# AutoCar.net
KiCad netlist of a schematic drawn in Altium Designer
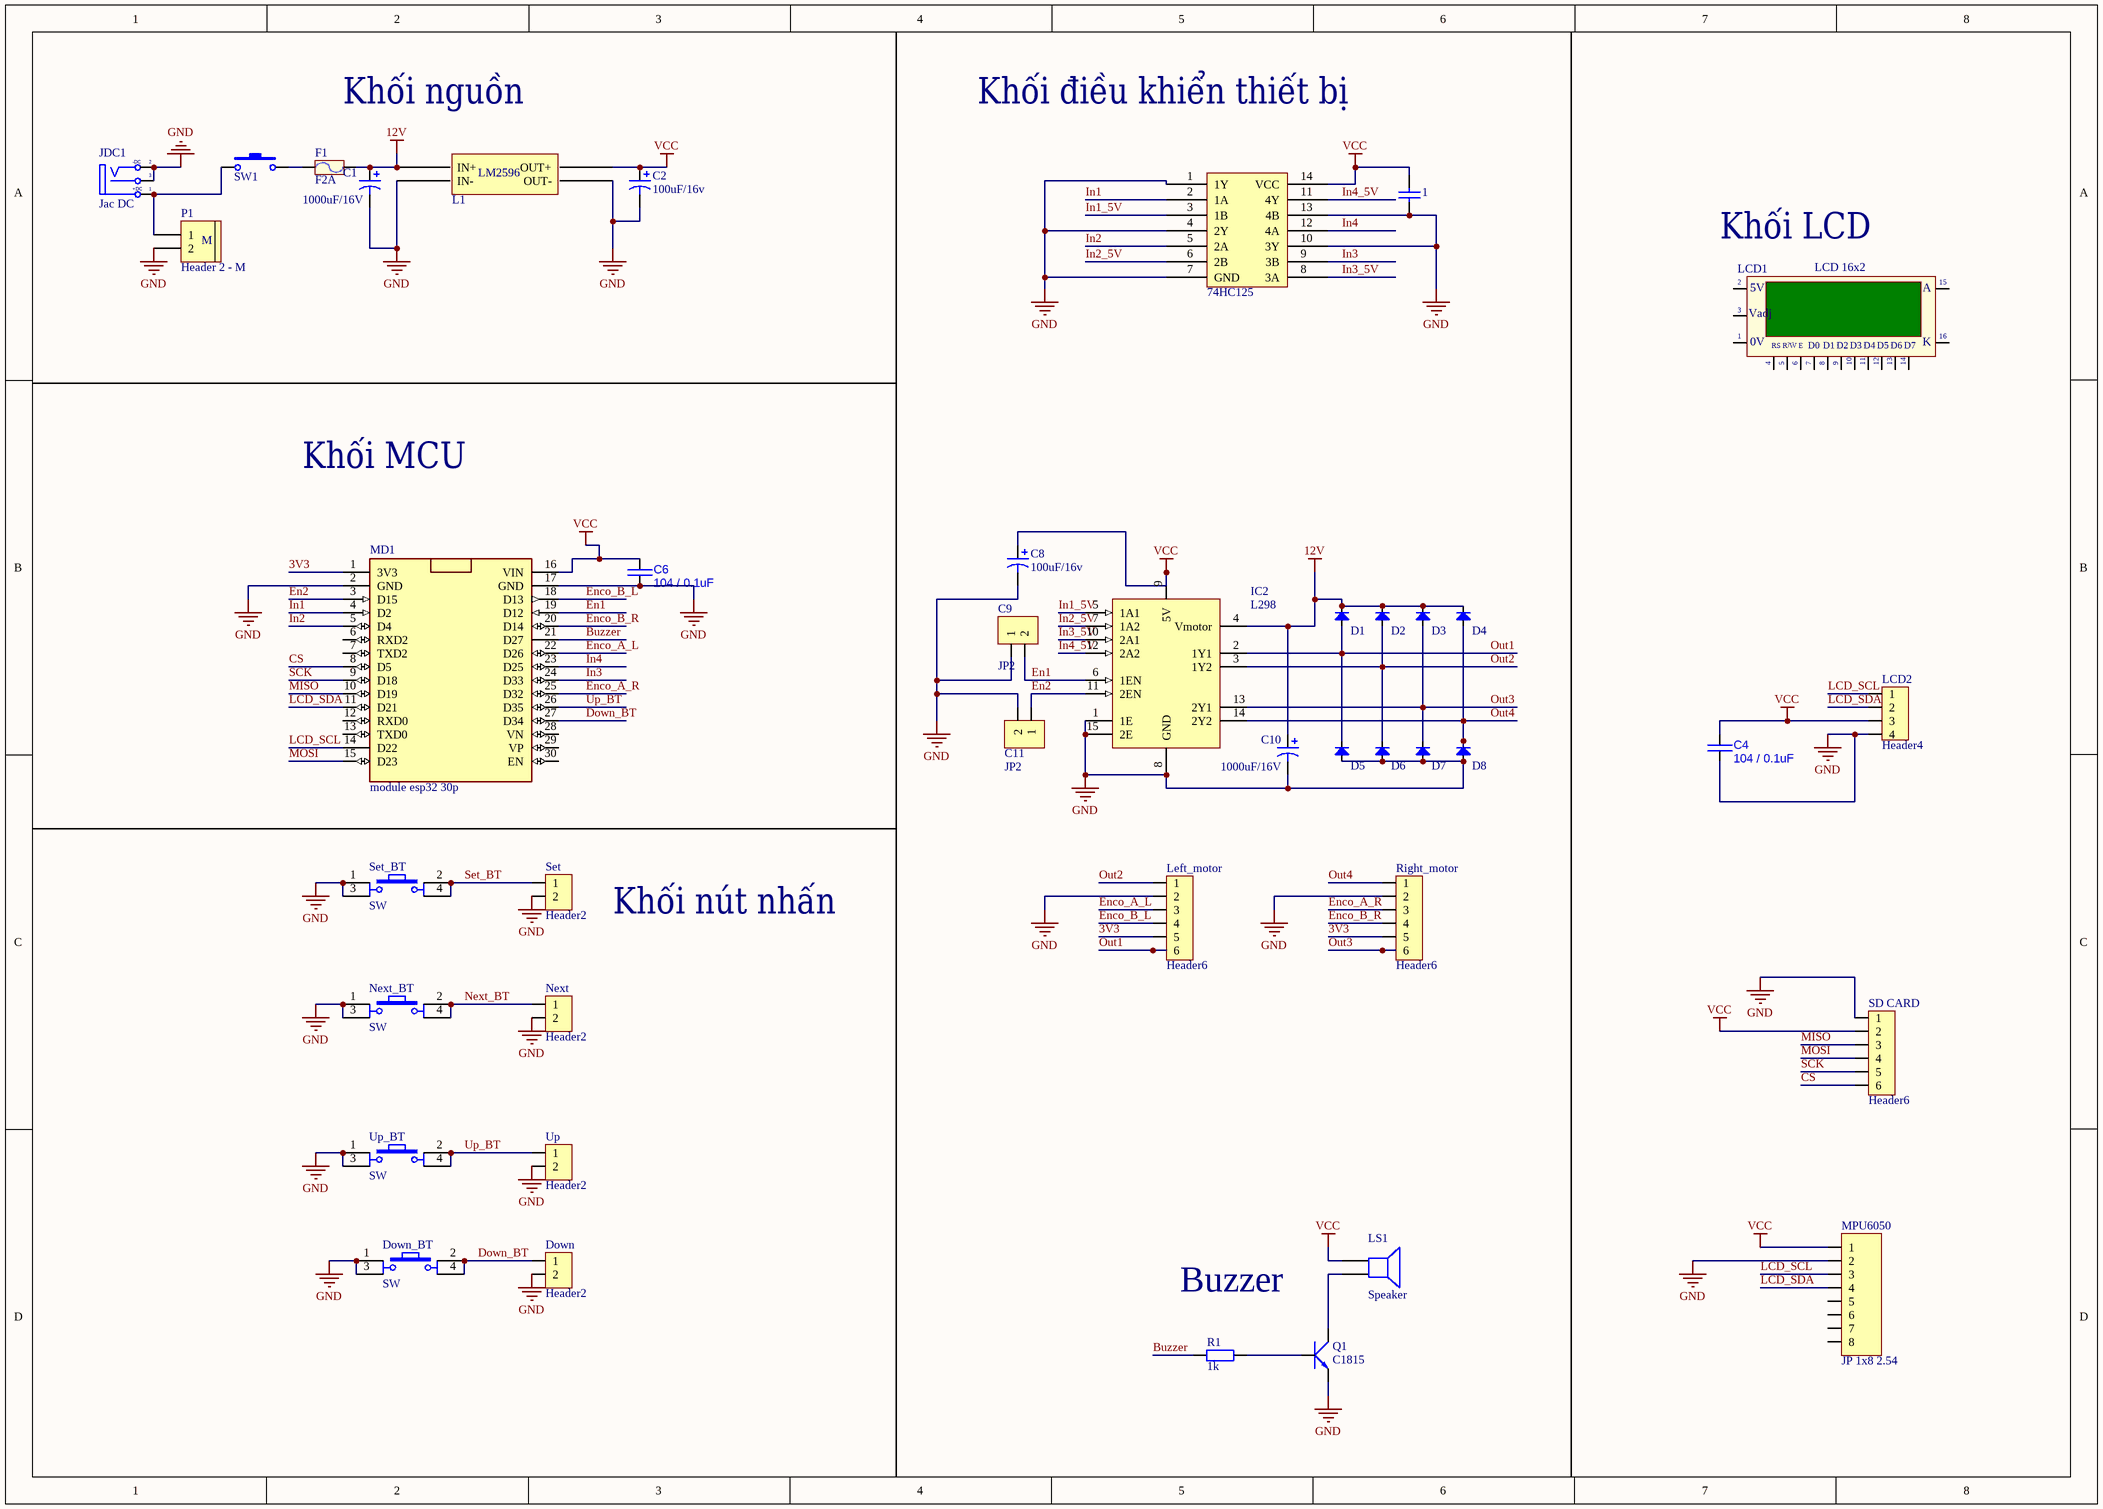
[diagram p0: AutoCar.SchDoc]

(export (version "E")
  (design (tool "Eeschema 10.0.6"))
  (components
    (comp (ref "1")
      (value "Capacitor Ceramic")
      (footprint "C1206")
      (description "Capacitor")
      (fields (field (name "PUBLISHER") "Altium Limited"))
      (libsource (lib "My Library") (part "CapSMD"))
    )
    (comp (ref "74HC125")
      (value "74HC02 DIP14")
      (footprint "dip14")
      (description "Cắm")
      (libsource (lib "IC") (part "74HC02 DIP"))
    )
    (comp (ref "C1")
      (value "1000uF/16V")
      (footprint "C8mm")
      (description "Polarized Capacitor (Axial)")
      (fields (field (name "PUBLISHER") "Altium Limited"))
      (libsource (lib "My Library") (part "Cap Pol 12mm"))
    )
    (comp (ref "C2")
      (value "100uF/16v")
      (footprint "C5mm")
      (description "Polarized Capacitor (Axial)")
      (fields (field (name "PUBLISHER") "Altium Limited"))
      (libsource (lib "My Library") (part "Cap Pol 5mm"))
    )
    (comp (ref "C4")
      (value "104 / 0.1uF")
      (footprint "SMD Capacistor 1206")
      (description "Capacitor SMD Cer 1.8nF 10% 50V X7R 0805")
      (fields (field (name "TOLERANCE") "±10%") (field (name "Comment") "approved sub OK"))
      (libsource (lib "My library altium") (part "CAP C_0805"))
    )
    (comp (ref "C6")
      (value "104 / 0.1uF")
      (footprint "SMD Capacistor 1206")
      (description "Capacitor SMD Cer 1.8nF 10% 50V X7R 0805")
      (fields (field (name "TOLERANCE") "±10%") (field (name "Comment") "approved sub OK"))
      (libsource (lib "My library altium") (part "CAP C_0805"))
    )
    (comp (ref "C8")
      (value "100uF/16v")
      (footprint "C5mm")
      (description "Polarized Capacitor (Axial)")
      (fields (field (name "PUBLISHER") "Altium Limited"))
      (libsource (lib "My Library") (part "Cap Pol 5mm"))
    )
    (comp (ref "C9")
      (value "JP2")
      (footprint "JP2-CLOSED")
      (description "WR-PHD 2.54 mm Angled Socket Header")
      (fields
        (field (name "MANUFACTURER") "Würth Elektronik eiSos GmbH")
        (field (name "PARTNO") "613002143121")
        (field (name "CREATED BY") "Karrer Zheng")
      )
      (libsource (lib "") (part "JP2_1"))
    )
    (comp (ref "C10")
      (value "1000uF/16V")
      (footprint "C8mm")
      (description "Polarized Capacitor (Axial)")
      (fields (field (name "PUBLISHER") "Altium Limited"))
      (libsource (lib "My Library") (part "Cap Pol 12mm"))
    )
    (comp (ref "C11")
      (value "JP2")
      (footprint "JP2-CLOSED")
      (description "WR-PHD 2.54 mm Angled Socket Header")
      (fields
        (field (name "MANUFACTURER") "Würth Elektronik eiSos GmbH")
        (field (name "PARTNO") "613002143121")
        (field (name "CREATED BY") "Karrer Zheng")
      )
      (libsource (lib "My Library") (part "JP2"))
    )
    (comp (ref "D1")
      (value "Diode SMD")
      (footprint "DIO-SMD-106")
      (description "Default Diode")
      (fields (field (name "PUBLISHER") "Altium Limited"))
      (libsource (lib "My Library") (part "Diode SMD"))
    )
    (comp (ref "D2")
      (value "Diode SMD")
      (footprint "DIO-SMD-106")
      (description "Default Diode")
      (fields (field (name "PUBLISHER") "Altium Limited"))
      (libsource (lib "My Library") (part "Diode SMD"))
    )
    (comp (ref "D3")
      (value "Diode SMD")
      (footprint "DIO-SMD-106")
      (description "Default Diode")
      (fields (field (name "PUBLISHER") "Altium Limited"))
      (libsource (lib "My Library") (part "Diode SMD"))
    )
    (comp (ref "D4")
      (value "Diode SMD")
      (footprint "DIO-SMD-106")
      (description "Default Diode")
      (fields (field (name "PUBLISHER") "Altium Limited"))
      (libsource (lib "My Library") (part "Diode SMD"))
    )
    (comp (ref "D5")
      (value "Diode SMD")
      (footprint "DIO-SMD-106")
      (description "Default Diode")
      (fields (field (name "PUBLISHER") "Altium Limited"))
      (libsource (lib "My Library") (part "Diode SMD"))
    )
    (comp (ref "D6")
      (value "Diode SMD")
      (footprint "DIO-SMD-106")
      (description "Default Diode")
      (fields (field (name "PUBLISHER") "Altium Limited"))
      (libsource (lib "My Library") (part "Diode SMD"))
    )
    (comp (ref "D7")
      (value "Diode SMD")
      (footprint "DIO-SMD-106")
      (description "Default Diode")
      (fields (field (name "PUBLISHER") "Altium Limited"))
      (libsource (lib "My Library") (part "Diode SMD"))
    )
    (comp (ref "D8")
      (value "Diode SMD")
      (footprint "DIO-SMD-106")
      (description "Default Diode")
      (fields (field (name "PUBLISHER") "Altium Limited"))
      (libsource (lib "My Library") (part "Diode SMD"))
    )
    (comp (ref "Down")
      (value "Header2")
      (footprint "Header2")
      (description "Header IDC, 2 x 1 Pin Vertical 2.54mm Pitch (Non-Boxed, Male)")
      (fields
        (field (name "MANUFACTURER") "Würth Elektronik eiSos GmbH")
        (field (name "PARTNO") "613002143121")
        (field (name "CREATED BY") "Karrer Zheng")
      )
      (libsource (lib "My Library") (part "Header2"))
    )
    (comp (ref "Down_BT")
      (value "SW")
      (footprint "SW4")
      (description "Switch button 4 pin")
      (libsource (lib "My Library (1)") (part "SW4"))
    )
    (comp (ref "F1")
      (value "F2A")
      (footprint "Fuse")
      (description "Fuse")
      (fields (field (name "DESIGNED BY") "VanDungEvn"))
      (libsource (lib "My Library") (part "Fuse"))
    )
    (comp (ref "IC2")
      (value "L298")
      (footprint "DIP15SL2")
      (description "Dual Full-H Driver")
      (fields (field (name "PUBLISHER") "Altium Limited"))
      (libsource (lib "My Library") (part "L298"))
    )
    (comp (ref "JDC1")
      (value "Jac DC")
      (footprint "DC-IN")
      (description "Jac DC input")
      (libsource (lib "My Library") (part "DCIN"))
    )
    (comp (ref "L1")
      (value "BUCK_LM2596")
      (footprint "BUCK_LM2596")
      (libsource (lib "BUCK_LM2596_Sch") (part "BUCK_LM2596"))
    )
    (comp (ref "LCD1")
      (value "LCD 16x2")
      (footprint "LCD16X2N")
      (libsource (lib "My library altium") (part "LCD"))
    )
    (comp (ref "LCD2")
      (value "Header4")
      (footprint "XH2.54M-4")
      (description "Header IDC, 4 x 1 Pin Vertical 2.54mm Pitch (Non-Boxed, Male)")
      (fields
        (field (name "MANUFACTURER") "Würth Elektronik eiSos GmbH")
        (field (name "PARTNO") "613002143121")
        (field (name "CREATED BY") "Karrer Zheng")
      )
      (libsource (lib "My Library") (part "Header4"))
    )
    (comp (ref "Left_motor")
      (value "Header6")
      (footprint "Header6")
      (description "Header IDC, 6 x 1 Pin Vertical 2.54mm Pitch (Non-Boxed, Male)")
      (fields
        (field (name "MANUFACTURER") "Würth Elektronik eiSos GmbH")
        (field (name "PARTNO") "613002143121")
        (field (name "CREATED BY") "Karrer Zheng")
      )
      (libsource (lib "My Library") (part "Header6"))
    )
    (comp (ref "LS1")
      (value "Speaker")
      (footprint "SPEAKER")
      (description "Loudspeaker")
      (fields (field (name "PUBLISHER") "Altium Limited"))
      (libsource (lib "My Library") (part "Speaker"))
    )
    (comp (ref "MD1")
      (value "module esp32 30p")
      (footprint "module esp32 30 pin")
      (libsource (lib "Chuong Engineer") (part "module esp32 30p"))
    )
    (comp (ref "MPU6050")
      (value "JP 1x8 2.54")
      (footprint "JP 1x8 CT")
      (description "Cắm")
      (libsource (lib "Altium_Lib_by_KhueNguyenCreator") (part "JP 1x8 2.54 Cai Thang"))
    )
    (comp (ref "Next")
      (value "Header2")
      (footprint "Header2")
      (description "Header IDC, 2 x 1 Pin Vertical 2.54mm Pitch (Non-Boxed, Male)")
      (fields
        (field (name "MANUFACTURER") "Würth Elektronik eiSos GmbH")
        (field (name "PARTNO") "613002143121")
        (field (name "CREATED BY") "Karrer Zheng")
      )
      (libsource (lib "My Library") (part "Header2"))
    )
    (comp (ref "Next_BT")
      (value "SW")
      (footprint "SW4")
      (description "Switch button 4 pin")
      (libsource (lib "My Library (1)") (part "SW4"))
    )
    (comp (ref "P1")
      (value "Header 2 - M")
      (footprint "Medium - Header 2")
      (description "Header, 2-Pin, Medium")
      (fields (field (name "PUBLISHER") "Altium Limited"))
      (libsource (lib "My Library") (part "Header 2 - M"))
    )
    (comp (ref "Q1")
      (value "C1815")
      (footprint "SOT23B")
      (description "NPN 600mW, ECB")
      (libsource (lib "syhaunguyen") (part "C1815"))
    )
    (comp (ref "R1")
      (value "1k")
      (footprint "RES-SMD-1206")
      (description "Resistor SMD 0805")
      (fields (field (name "PUBLISHER") "Altium Limited"))
      (libsource (lib "My Library (1)") (part "R0805"))
    )
    (comp (ref "Right_motor")
      (value "Header6")
      (footprint "Header6")
      (description "Header IDC, 6 x 1 Pin Vertical 2.54mm Pitch (Non-Boxed, Male)")
      (fields
        (field (name "MANUFACTURER") "Würth Elektronik eiSos GmbH")
        (field (name "PARTNO") "613002143121")
        (field (name "CREATED BY") "Karrer Zheng")
      )
      (libsource (lib "My Library") (part "Header6"))
    )
    (comp (ref "SD CARD")
      (value "Header6")
      (footprint "Header6")
      (description "Header IDC, 6 x 1 Pin Vertical 2.54mm Pitch (Non-Boxed, Male)")
      (fields
        (field (name "MANUFACTURER") "Würth Elektronik eiSos GmbH")
        (field (name "PARTNO") "613002143121")
        (field (name "CREATED BY") "Karrer Zheng")
      )
      (libsource (lib "My Library") (part "Header6"))
    )
    (comp (ref "Set")
      (value "Header2")
      (footprint "Header2")
      (description "Header IDC, 2 x 1 Pin Vertical 2.54mm Pitch (Non-Boxed, Male)")
      (fields
        (field (name "MANUFACTURER") "Würth Elektronik eiSos GmbH")
        (field (name "PARTNO") "613002143121")
        (field (name "CREATED BY") "Karrer Zheng")
      )
      (libsource (lib "My Library") (part "Header2"))
    )
    (comp (ref "Set_BT")
      (value "SW")
      (footprint "SW4")
      (description "Switch button 4 pin")
      (libsource (lib "My Library (1)") (part "SW4"))
    )
    (comp (ref "SW1")
      (value "KCD01-11_SWITCH")
      (footprint "KCD01-11")
      (description "Nut Nhan 2 Chan SMD 3x6x2.5")
      (libsource (lib "KS Chuong") (part "KCD01-11_SWITCH"))
    )
    (comp (ref "Up")
      (value "Header2")
      (footprint "Header2")
      (description "Header IDC, 2 x 1 Pin Vertical 2.54mm Pitch (Non-Boxed, Male)")
      (fields
        (field (name "MANUFACTURER") "Würth Elektronik eiSos GmbH")
        (field (name "PARTNO") "613002143121")
        (field (name "CREATED BY") "Karrer Zheng")
      )
      (libsource (lib "My Library") (part "Header2"))
    )
    (comp (ref "Up_BT")
      (value "SW")
      (footprint "SW4")
      (description "Switch button 4 pin")
      (libsource (lib "My Library (1)") (part "SW4"))
    )
  )
  (nets
    (net (code "1") (name "/3V3") (class "Default")
      (node (ref "Left_motor") (pin "5") (pinfunction "5_5") (pintype "passive"))
      (node (ref "MD1") (pin "1") (pinfunction "3V3_1") (pintype "power_in"))
      (node (ref "Right_motor") (pin "5") (pinfunction "5_5") (pintype "passive"))
    )
    (net (code "2") (name "/Buzzer") (class "Default")
      (node (ref "MD1") (pin "21") (pinfunction "D27_21") (pintype "power_in"))
      (node (ref "R1") (pin "2") (pinfunction "2_2") (pintype "passive"))
    )
    (net (code "3") (name "/CS") (class "Default")
      (node (ref "MD1") (pin "8") (pinfunction "D5_8") (pintype "bidirectional"))
      (node (ref "SD CARD") (pin "6") (pinfunction "6_6") (pintype "passive"))
    )
    (net (code "4") (name "/Down_BT") (class "Default")
      (node (ref "Down") (pin "1") (pinfunction "1_1") (pintype "passive"))
      (node (ref "Down_BT") (pin "2") (pintype "passive"))
      (node (ref "Down_BT") (pin "4") (pintype "passive"))
      (node (ref "MD1") (pin "27") (pinfunction "D34_27") (pintype "bidirectional"))
    )
    (net (code "5") (name "/En1") (class "Default")
      (node (ref "C9") (pin "2") (pinfunction "2_2") (pintype "passive"))
      (node (ref "IC2") (pin "6") (pinfunction "1EN_6") (pintype "input"))
      (node (ref "MD1") (pin "19") (pinfunction "D12_19") (pintype "input"))
    )
    (net (code "6") (name "/En2") (class "Default")
      (node (ref "C11") (pin "1") (pinfunction "1_1") (pintype "passive"))
      (node (ref "IC2") (pin "11") (pinfunction "2EN_11") (pintype "input"))
      (node (ref "MD1") (pin "3") (pinfunction "D15_3") (pintype "input"))
    )
    (net (code "7") (name "/Enco_A_L") (class "Default")
      (node (ref "Left_motor") (pin "3") (pinfunction "3_3") (pintype "passive"))
      (node (ref "MD1") (pin "22") (pinfunction "D26_22") (pintype "bidirectional"))
    )
    (net (code "8") (name "/Enco_A_R") (class "Default")
      (node (ref "MD1") (pin "25") (pinfunction "D32_25") (pintype "bidirectional"))
      (node (ref "Right_motor") (pin "3") (pinfunction "3_3") (pintype "passive"))
    )
    (net (code "9") (name "/Enco_B_L") (class "Default")
      (node (ref "Left_motor") (pin "4") (pinfunction "4_4") (pintype "passive"))
      (node (ref "MD1") (pin "18") (pinfunction "D13_18") (pintype "output"))
    )
    (net (code "10") (name "/Enco_B_R") (class "Default")
      (node (ref "MD1") (pin "20") (pinfunction "D14_20") (pintype "bidirectional"))
      (node (ref "Right_motor") (pin "4") (pinfunction "4_4") (pintype "passive"))
    )
    (net (code "11") (name "/In1") (class "Default")
      (node (ref "74HC125") (pin "2") (pinfunction "1A_2") (pintype "passive"))
      (node (ref "MD1") (pin "4") (pinfunction "D2_4") (pintype "input"))
    )
    (net (code "12") (name "/In1_5V") (class "Default")
      (node (ref "74HC125") (pin "3") (pinfunction "1B_3") (pintype "passive"))
      (node (ref "IC2") (pin "5") (pinfunction "1A1_5") (pintype "input"))
    )
    (net (code "13") (name "/In2") (class "Default")
      (node (ref "74HC125") (pin "5") (pinfunction "2A_5") (pintype "passive"))
      (node (ref "MD1") (pin "5") (pinfunction "D4_5") (pintype "bidirectional"))
    )
    (net (code "14") (name "/In2_5V") (class "Default")
      (node (ref "74HC125") (pin "6") (pinfunction "2B_6") (pintype "passive"))
      (node (ref "IC2") (pin "7") (pinfunction "1A2_7") (pintype "input"))
    )
    (net (code "15") (name "/In3") (class "Default")
      (node (ref "74HC125") (pin "9") (pinfunction "3B_9") (pintype "passive"))
      (node (ref "MD1") (pin "24") (pinfunction "D33_24") (pintype "bidirectional"))
    )
    (net (code "16") (name "/In3_5V") (class "Default")
      (node (ref "74HC125") (pin "8") (pinfunction "3A_8") (pintype "passive"))
      (node (ref "IC2") (pin "10") (pinfunction "2A1_10") (pintype "input"))
    )
    (net (code "17") (name "/In4") (class "Default")
      (node (ref "74HC125") (pin "12") (pinfunction "4A_12") (pintype "passive"))
      (node (ref "MD1") (pin "23") (pinfunction "D25_23") (pintype "bidirectional"))
    )
    (net (code "18") (name "/In4_5V") (class "Default")
      (node (ref "74HC125") (pin "11") (pinfunction "4Y_11") (pintype "passive"))
      (node (ref "IC2") (pin "12") (pinfunction "2A2_12") (pintype "input"))
    )
    (net (code "19") (name "/LCD_SCL") (class "Default")
      (node (ref "LCD2") (pin "1") (pinfunction "1_1") (pintype "passive"))
      (node (ref "MD1") (pin "14") (pinfunction "D22_14") (pintype "power_in"))
      (node (ref "MPU6050") (pin "3") (pinfunction "3_3") (pintype "passive"))
    )
    (net (code "20") (name "/LCD_SDA") (class "Default")
      (node (ref "LCD2") (pin "2") (pinfunction "2_2") (pintype "passive"))
      (node (ref "MD1") (pin "11") (pinfunction "D21_11") (pintype "bidirectional"))
      (node (ref "MPU6050") (pin "4") (pinfunction "4_4") (pintype "passive"))
    )
    (net (code "21") (name "/MISO") (class "Default")
      (node (ref "MD1") (pin "10") (pinfunction "D19_10") (pintype "bidirectional"))
      (node (ref "SD CARD") (pin "3") (pinfunction "3_3") (pintype "passive"))
    )
    (net (code "22") (name "/MOSI") (class "Default")
      (node (ref "MD1") (pin "15") (pinfunction "D23_15") (pintype "bidirectional"))
      (node (ref "SD CARD") (pin "4") (pinfunction "4_4") (pintype "passive"))
    )
    (net (code "23") (name "/Next_BT") (class "Default")
      (node (ref "Next") (pin "1") (pinfunction "1_1") (pintype "passive"))
      (node (ref "Next_BT") (pin "2") (pintype "passive"))
      (node (ref "Next_BT") (pin "4") (pintype "passive"))
    )
    (net (code "24") (name "/Out1") (class "Default")
      (node (ref "D1") (pin "1") (pinfunction "A_1") (pintype "passive"))
      (node (ref "D5") (pin "2") (pinfunction "K_2") (pintype "passive"))
      (node (ref "IC2") (pin "2") (pinfunction "1Y1_2") (pintype "tri_state"))
      (node (ref "Left_motor") (pin "6") (pinfunction "6_6") (pintype "passive"))
    )
    (net (code "25") (name "/Out2") (class "Default")
      (node (ref "D2") (pin "1") (pinfunction "A_1") (pintype "passive"))
      (node (ref "D6") (pin "2") (pinfunction "K_2") (pintype "passive"))
      (node (ref "IC2") (pin "3") (pinfunction "1Y2_3") (pintype "tri_state"))
      (node (ref "Left_motor") (pin "1") (pinfunction "1_1") (pintype "passive"))
    )
    (net (code "26") (name "/Out3") (class "Default")
      (node (ref "D3") (pin "1") (pinfunction "A_1") (pintype "passive"))
      (node (ref "D7") (pin "2") (pinfunction "K_2") (pintype "passive"))
      (node (ref "IC2") (pin "13") (pinfunction "2Y1_13") (pintype "tri_state"))
      (node (ref "Right_motor") (pin "6") (pinfunction "6_6") (pintype "passive"))
    )
    (net (code "27") (name "/Out4") (class "Default")
      (node (ref "D4") (pin "1") (pinfunction "A_1") (pintype "passive"))
      (node (ref "D8") (pin "2") (pinfunction "K_2") (pintype "passive"))
      (node (ref "IC2") (pin "14") (pinfunction "2Y2_14") (pintype "tri_state"))
      (node (ref "Right_motor") (pin "1") (pinfunction "1_1") (pintype "passive"))
    )
    (net (code "28") (name "/SCK") (class "Default")
      (node (ref "MD1") (pin "9") (pinfunction "D18_9") (pintype "bidirectional"))
      (node (ref "SD CARD") (pin "5") (pinfunction "5_5") (pintype "passive"))
    )
    (net (code "29") (name "/Set_BT") (class "Default")
      (node (ref "Set") (pin "1") (pinfunction "1_1") (pintype "passive"))
      (node (ref "Set_BT") (pin "2") (pintype "passive"))
      (node (ref "Set_BT") (pin "4") (pintype "passive"))
    )
    (net (code "30") (name "/Up_BT") (class "Default")
      (node (ref "MD1") (pin "26") (pinfunction "D35_26") (pintype "bidirectional"))
      (node (ref "Up") (pin "1") (pinfunction "1_1") (pintype "passive"))
      (node (ref "Up_BT") (pin "2") (pintype "passive"))
      (node (ref "Up_BT") (pin "4") (pintype "passive"))
    )
    (net (code "31") (name "12V") (class "Default")
      (node (ref "C1") (pin "1") (pinfunction "1_1") (pintype "passive"))
      (node (ref "C10") (pin "1") (pinfunction "1_1") (pintype "passive"))
      (node (ref "D1") (pin "2") (pinfunction "K_2") (pintype "passive"))
      (node (ref "D2") (pin "2") (pinfunction "K_2") (pintype "passive"))
      (node (ref "D3") (pin "2") (pinfunction "K_2") (pintype "passive"))
      (node (ref "D4") (pin "2") (pinfunction "K_2") (pintype "passive"))
      (node (ref "F1") (pin "2") (pinfunction "2_2") (pintype "passive"))
      (node (ref "IC2") (pin "4") (pinfunction "Vmotor_4") (pintype "power_in"))
      (node (ref "L1") (pin "1") (pinfunction "IN+_1") (pintype "passive"))
    )
    (net (code "32") (name "GND") (class "Default")
      (node (ref "1") (pin "1") (pinfunction "1_1") (pintype "passive"))
      (node (ref "74HC125") (pin "1") (pinfunction "1Y_1") (pintype "passive"))
      (node (ref "74HC125") (pin "10") (pinfunction "3Y_10") (pintype "passive"))
      (node (ref "74HC125") (pin "13") (pinfunction "4B_13") (pintype "passive"))
      (node (ref "74HC125") (pin "4") (pinfunction "2Y_4") (pintype "passive"))
      (node (ref "74HC125") (pin "7") (pinfunction "GND_7") (pintype "passive"))
      (node (ref "C1") (pin "2") (pinfunction "2_2") (pintype "passive"))
      (node (ref "C10") (pin "2") (pinfunction "2_2") (pintype "passive"))
      (node (ref "C11") (pin "2") (pinfunction "2_2") (pintype "passive"))
      (node (ref "C2") (pin "2") (pinfunction "2_2") (pintype "passive"))
      (node (ref "C4") (pin "1") (pintype "passive"))
      (node (ref "C6") (pin "1") (pintype "passive"))
      (node (ref "C8") (pin "2") (pinfunction "2_2") (pintype "passive"))
      (node (ref "C9") (pin "1") (pinfunction "1_1") (pintype "passive"))
      (node (ref "D5") (pin "1") (pinfunction "A_1") (pintype "passive"))
      (node (ref "D6") (pin "1") (pinfunction "A_1") (pintype "passive"))
      (node (ref "D7") (pin "1") (pinfunction "A_1") (pintype "passive"))
      (node (ref "D8") (pin "1") (pinfunction "A_1") (pintype "passive"))
      (node (ref "Down") (pin "2") (pinfunction "2_2") (pintype "passive"))
      (node (ref "Down_BT") (pin "1") (pintype "passive"))
      (node (ref "Down_BT") (pin "3") (pintype "passive"))
      (node (ref "IC2") (pin "1") (pinfunction "1E_1") (pintype "passive"))
      (node (ref "IC2") (pin "15") (pinfunction "2E_15") (pintype "passive"))
      (node (ref "IC2") (pin "8") (pinfunction "GND_8") (pintype "power_in"))
      (node (ref "JDC1") (pin "2") (pinfunction "TN_2") (pintype "passive"))
      (node (ref "JDC1") (pin "3") (pinfunction "S_3") (pintype "power_in"))
      (node (ref "L1") (pin "2") (pinfunction "IN-_2") (pintype "passive"))
      (node (ref "L1") (pin "3") (pinfunction "OUT-_3") (pintype "passive"))
      (node (ref "LCD2") (pin "4") (pinfunction "4_4") (pintype "passive"))
      (node (ref "Left_motor") (pin "2") (pinfunction "2_2") (pintype "passive"))
      (node (ref "MD1") (pin "17") (pinfunction "GND_17") (pintype "power_in"))
      (node (ref "MD1") (pin "2") (pinfunction "GND_2") (pintype "power_in"))
      (node (ref "MPU6050") (pin "2") (pinfunction "2_2") (pintype "passive"))
      (node (ref "Next") (pin "2") (pinfunction "2_2") (pintype "passive"))
      (node (ref "Next_BT") (pin "1") (pintype "passive"))
      (node (ref "Next_BT") (pin "3") (pintype "passive"))
      (node (ref "P1") (pin "2") (pinfunction "2_2") (pintype "passive"))
      (node (ref "Q1") (pin "1") (pinfunction "E_1") (pintype "passive"))
      (node (ref "Right_motor") (pin "2") (pinfunction "2_2") (pintype "passive"))
      (node (ref "SD CARD") (pin "1") (pinfunction "1_1") (pintype "passive"))
      (node (ref "Set") (pin "2") (pinfunction "2_2") (pintype "passive"))
      (node (ref "Set_BT") (pin "1") (pintype "passive"))
      (node (ref "Set_BT") (pin "3") (pintype "passive"))
      (node (ref "Up") (pin "2") (pinfunction "2_2") (pintype "passive"))
      (node (ref "Up_BT") (pin "1") (pintype "passive"))
      (node (ref "Up_BT") (pin "3") (pintype "passive"))
    )
    (net (code "33") (name "Net-(F1-Pad1)") (class "Default")
      (node (ref "F1") (pin "1") (pinfunction "1_1") (pintype "passive"))
      (node (ref "SW1") (pin "2") (pinfunction "2_2") (pintype "passive"))
    )
    (net (code "34") (name "Net-(JDC1-T)") (class "Default")
      (node (ref "JDC1") (pin "1") (pinfunction "T_1") (pintype "passive"))
      (node (ref "P1") (pin "1") (pinfunction "1_1") (pintype "passive"))
      (node (ref "SW1") (pin "1") (pinfunction "1_1") (pintype "passive"))
    )
    (net (code "35") (name "Net-(Q1-B)") (class "Default")
      (node (ref "Q1") (pin "3") (pinfunction "B_3") (pintype "passive"))
      (node (ref "R1") (pin "1") (pinfunction "1_1") (pintype "passive"))
    )
    (net (code "36") (name "Net-(Q1-C)") (class "Default")
      (node (ref "LS1") (pin "2") (pinfunction "2_2") (pintype "passive"))
      (node (ref "Q1") (pin "2") (pinfunction "C_2") (pintype "passive"))
    )
    (net (code "37") (name "VCC") (class "Default")
      (node (ref "1") (pin "2") (pinfunction "2_2") (pintype "passive"))
      (node (ref "74HC125") (pin "14") (pinfunction "VCC_14") (pintype "passive"))
      (node (ref "C2") (pin "1") (pinfunction "1_1") (pintype "passive"))
      (node (ref "C4") (pin "2") (pintype "passive"))
      (node (ref "C6") (pin "2") (pintype "passive"))
      (node (ref "C8") (pin "1") (pinfunction "1_1") (pintype "passive"))
      (node (ref "IC2") (pin "9") (pinfunction "5V_9") (pintype "power_in"))
      (node (ref "L1") (pin "4") (pinfunction "OUT+_4") (pintype "passive"))
      (node (ref "LCD2") (pin "3") (pinfunction "3_3") (pintype "passive"))
      (node (ref "LS1") (pin "1") (pinfunction "1_1") (pintype "passive"))
      (node (ref "MD1") (pin "16") (pinfunction "VIN_16") (pintype "power_in"))
      (node (ref "MPU6050") (pin "1") (pinfunction "1_1") (pintype "passive"))
      (node (ref "SD CARD") (pin "2") (pinfunction "2_2") (pintype "passive"))
    )
    (net (code "38") (name "unconnected-(LCD1-A-Pad15)") (class "Default")
      (node (ref "LCD1") (pin "15") (pinfunction "A_15") (pintype "passive"))
    )
    (net (code "39") (name "unconnected-(LCD1-D0-Pad7)") (class "Default")
      (node (ref "LCD1") (pin "7") (pinfunction "D0_7") (pintype "passive"))
    )
    (net (code "40") (name "unconnected-(LCD1-D1-Pad8)") (class "Default")
      (node (ref "LCD1") (pin "8") (pinfunction "D1_8") (pintype "passive"))
    )
    (net (code "41") (name "unconnected-(LCD1-D2-Pad9)") (class "Default")
      (node (ref "LCD1") (pin "9") (pinfunction "D2_9") (pintype "passive"))
    )
    (net (code "42") (name "unconnected-(LCD1-D3-Pad10)") (class "Default")
      (node (ref "LCD1") (pin "10") (pinfunction "D3_10") (pintype "passive"))
    )
    (net (code "43") (name "unconnected-(LCD1-D4-Pad11)") (class "Default")
      (node (ref "LCD1") (pin "11") (pinfunction "D4_11") (pintype "passive"))
    )
    (net (code "44") (name "unconnected-(LCD1-D5-Pad12)") (class "Default")
      (node (ref "LCD1") (pin "12") (pinfunction "D5_12") (pintype "passive"))
    )
    (net (code "45") (name "unconnected-(LCD1-D6-Pad13)") (class "Default")
      (node (ref "LCD1") (pin "13") (pinfunction "D6_13") (pintype "passive"))
    )
    (net (code "46") (name "unconnected-(LCD1-D7-Pad14)") (class "Default")
      (node (ref "LCD1") (pin "14") (pinfunction "D7_14") (pintype "passive"))
    )
    (net (code "47") (name "unconnected-(LCD1-GND-Pad1)") (class "Default")
      (node (ref "LCD1") (pin "1") (pinfunction "GND_1") (pintype "passive"))
    )
    (net (code "48") (name "unconnected-(LCD1-K-Pad16)") (class "Default")
      (node (ref "LCD1") (pin "16") (pinfunction "K_16") (pintype "passive"))
    )
    (net (code "49") (name "unconnected-(LCD1-RS-Pad4)") (class "Default")
      (node (ref "LCD1") (pin "4") (pinfunction "RS_4") (pintype "passive"))
    )
    (net (code "50") (name "unconnected-(LCD1-R{slash}~{W}-Pad5)") (class "Default")
      (node (ref "LCD1") (pin "5") (pinfunction "R/~{W}_5") (pintype "passive"))
    )
    (net (code "51") (name "unconnected-(LCD1-VAdj-Pad3)") (class "Default")
      (node (ref "LCD1") (pin "3") (pinfunction "VAdj_3") (pintype "passive"))
    )
    (net (code "52") (name "unconnected-(LCD1-VDD-Pad2)") (class "Default")
      (node (ref "LCD1") (pin "2") (pinfunction "VDD_2") (pintype "passive"))
    )
    (net (code "53") (name "unconnected-(LCD1-~{EN}-Pad6)") (class "Default")
      (node (ref "LCD1") (pin "6") (pinfunction "~{EN}_6") (pintype "passive"))
    )
    (net (code "54") (name "unconnected-(MD1-EN-Pad30)") (class "Default")
      (node (ref "MD1") (pin "30") (pinfunction "EN_30") (pintype "bidirectional"))
    )
    (net (code "55") (name "unconnected-(MD1-RXD0-Pad12)") (class "Default")
      (node (ref "MD1") (pin "12") (pinfunction "RXD0_12") (pintype "bidirectional"))
    )
    (net (code "56") (name "unconnected-(MD1-RXD2-Pad6)") (class "Default")
      (node (ref "MD1") (pin "6") (pinfunction "RXD2_6") (pintype "bidirectional"))
    )
    (net (code "57") (name "unconnected-(MD1-TXD0-Pad13)") (class "Default")
      (node (ref "MD1") (pin "13") (pinfunction "TXD0_13") (pintype "bidirectional"))
    )
    (net (code "58") (name "unconnected-(MD1-TXD2-Pad7)") (class "Default")
      (node (ref "MD1") (pin "7") (pinfunction "TXD2_7") (pintype "bidirectional"))
    )
    (net (code "59") (name "unconnected-(MD1-VN-Pad28)") (class "Default")
      (node (ref "MD1") (pin "28") (pinfunction "VN_28") (pintype "bidirectional"))
    )
    (net (code "60") (name "unconnected-(MD1-VP-Pad29)") (class "Default")
      (node (ref "MD1") (pin "29") (pinfunction "VP_29") (pintype "bidirectional"))
    )
    (net (code "61") (name "unconnected-(MPU6050-Pad5)") (class "Default")
      (node (ref "MPU6050") (pin "5") (pinfunction "5_5") (pintype "passive"))
    )
    (net (code "62") (name "unconnected-(MPU6050-Pad6)") (class "Default")
      (node (ref "MPU6050") (pin "6") (pinfunction "6_6") (pintype "passive"))
    )
    (net (code "63") (name "unconnected-(MPU6050-Pad7)") (class "Default")
      (node (ref "MPU6050") (pin "7") (pinfunction "7_7") (pintype "passive"))
    )
    (net (code "64") (name "unconnected-(MPU6050-Pad8)") (class "Default")
      (node (ref "MPU6050") (pin "8") (pinfunction "8_8") (pintype "passive"))
    )
  )
)
